# hematicComputer.net
KiCad netlist of a schematic drawn in EAGLE
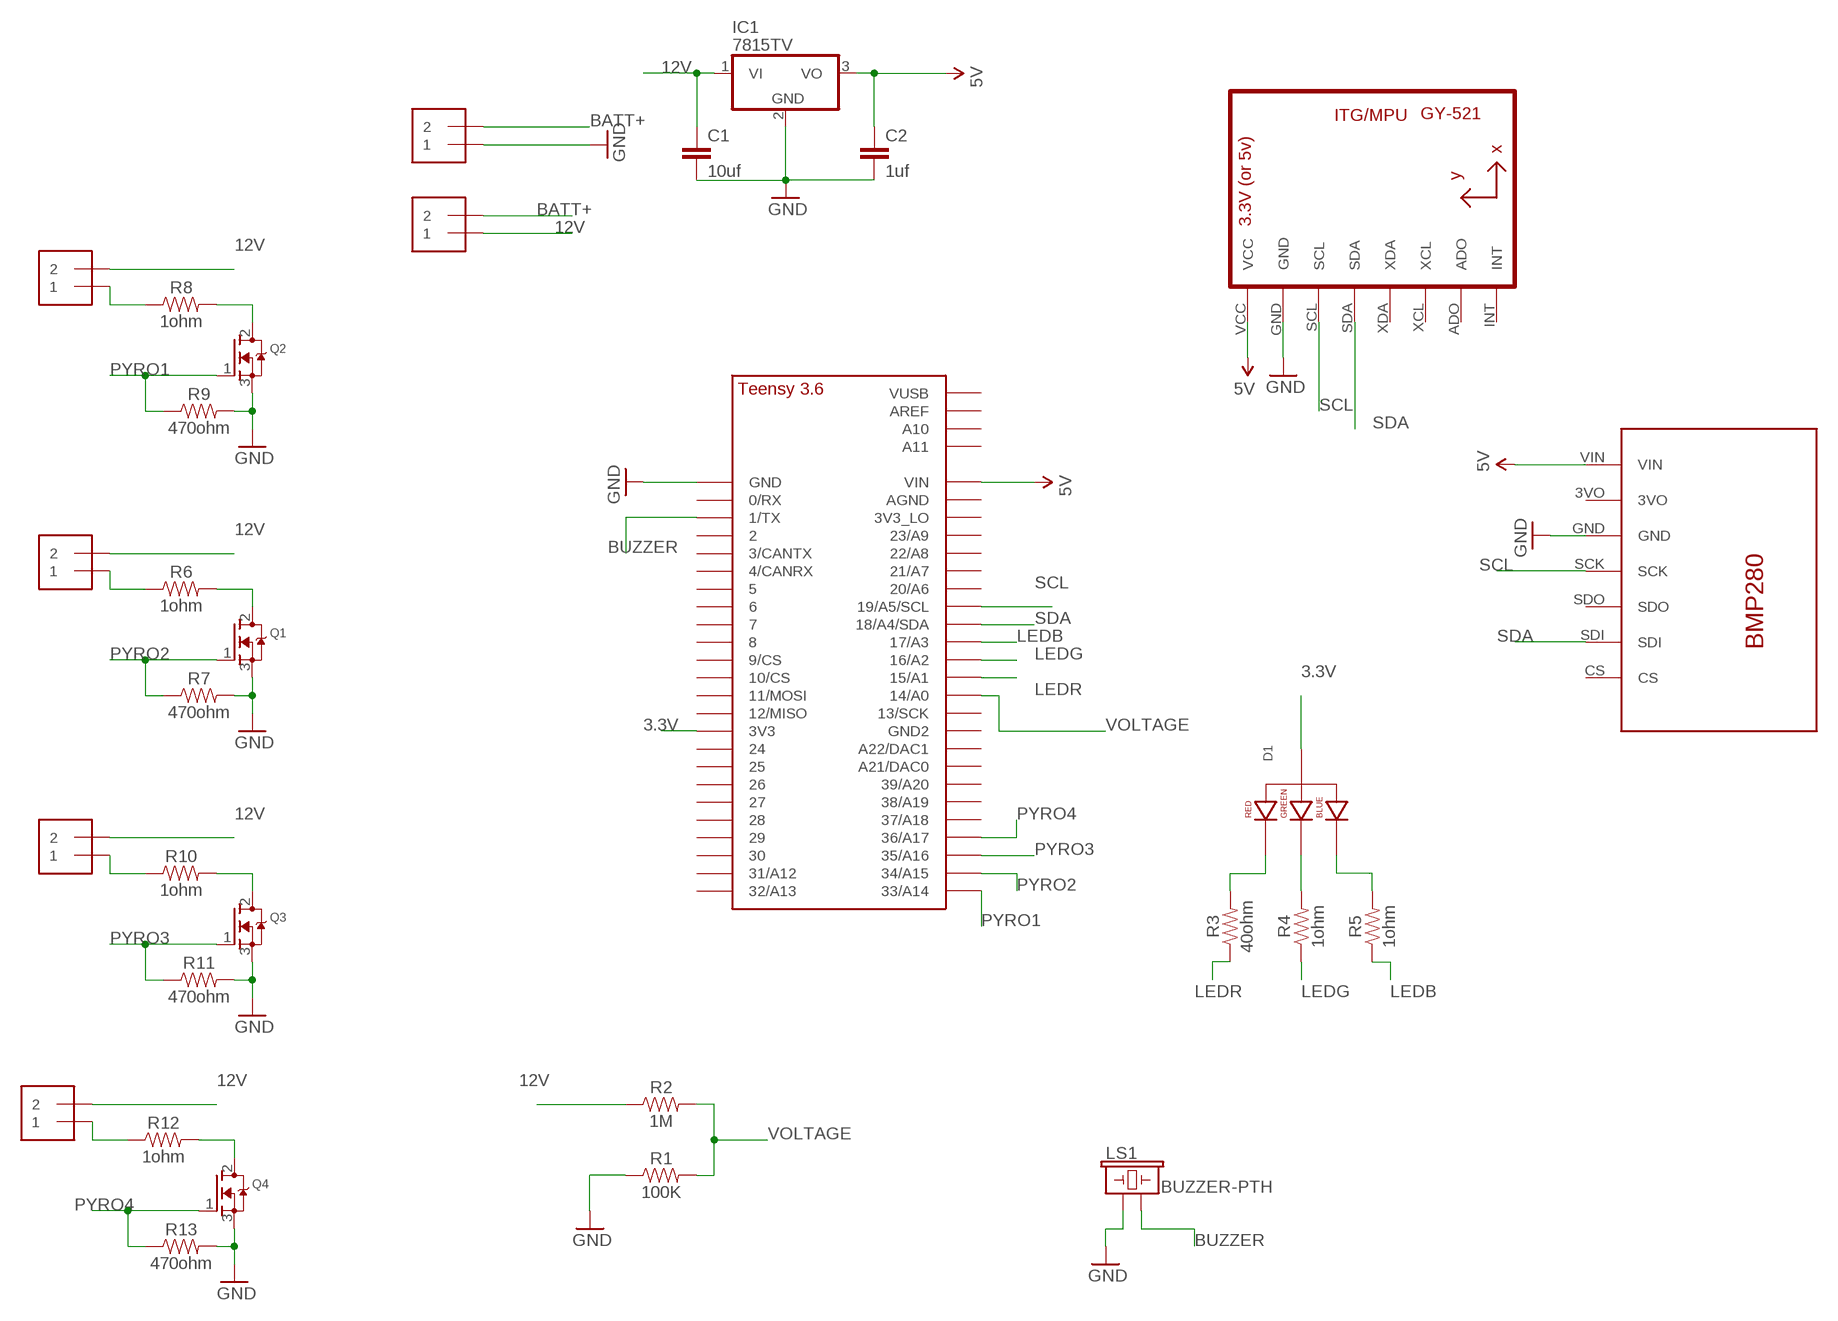
[diagram p0: schematic, sheet 1]

(export (version "E")
  (design (tool "Eeschema 10.0.6"))
  (components
    (comp (ref "C1")
      (value "10uf")
      (footprint "eagle-import:CAP-PTH-2.54")
      (libsource (lib "eagle-import") (part "22PF-PTH-2.54MM-200V-5%"))
    )
    (comp (ref "C2")
      (value "1uf")
      (footprint "eagle-import:CAP-PTH-2.54")
      (libsource (lib "eagle-import") (part "22PF-PTH-2.54MM-200V-5%"))
    )
    (comp (ref "D1")
      (value "LED-RGB-CA-THRUCLEAR")
      (footprint "eagle-import:LED-RGB-THRU")
      (libsource (lib "eagle-import") (part "LED-RGB-CA-THRUCLEAR"))
    )
    (comp (ref "IC1")
      (value "7815TV")
      (footprint "eagle-import:TO220V")
      (libsource (lib "eagle-import") (part "78TV15"))
    )
    (comp (ref "J1")
      (value "1X2-3.5MM")
      (footprint "eagle-import:1X2-3.5MM")
      (libsource (lib "eagle-import") (part "1X2-3.5MM"))
    )
    (comp (ref "J2")
      (value "1X2-3.5MM")
      (footprint "eagle-import:1X2-3.5MM")
      (libsource (lib "eagle-import") (part "1X2-3.5MM"))
    )
    (comp (ref "J3")
      (value "1X2-3.5MM")
      (footprint "eagle-import:1X2-3.5MM")
      (libsource (lib "eagle-import") (part "1X2-3.5MM"))
    )
    (comp (ref "J4")
      (value "1X2-3.5MM")
      (footprint "eagle-import:1X2-3.5MM")
      (libsource (lib "eagle-import") (part "1X2-3.5MM"))
    )
    (comp (ref "J5")
      (value "1X2-3.5MM")
      (footprint "eagle-import:1X2-3.5MM")
      (libsource (lib "eagle-import") (part "1X2-3.5MM"))
    )
    (comp (ref "J6")
      (value "1X2-3.5MM")
      (footprint "eagle-import:1X2-3.5MM")
      (libsource (lib "eagle-import") (part "1X2-3.5MM"))
    )
    (comp (ref "LS1")
      (value "BUZZER-PTH")
      (footprint "eagle-import:BUZZER-12MM")
      (libsource (lib "eagle-import") (part "BUZZER-PTH"))
    )
    (comp (ref "Q1")
      (value "MOSFET-NGDS_TO220V")
      (footprint "eagle-import:TO220V")
      (libsource (lib "eagle-import") (part "MOSFET-NGDS_TO220V"))
    )
    (comp (ref "Q2")
      (value "MOSFET-NGDS_TO220V")
      (footprint "eagle-import:TO220V")
      (libsource (lib "eagle-import") (part "MOSFET-NGDS_TO220V"))
    )
    (comp (ref "Q3")
      (value "MOSFET-NGDS_TO220V")
      (footprint "eagle-import:TO220V")
      (libsource (lib "eagle-import") (part "MOSFET-NGDS_TO220V"))
    )
    (comp (ref "Q4")
      (value "MOSFET-NGDS_TO220V")
      (footprint "eagle-import:TO220V")
      (libsource (lib "eagle-import") (part "MOSFET-NGDS_TO220V"))
    )
    (comp (ref "R1")
      (value "100K")
      (footprint "eagle-import:AXIAL-0.3")
      (libsource (lib "eagle-import") (part "10KOHM-HORIZ-1/4W-1%"))
    )
    (comp (ref "R2")
      (value "1M")
      (footprint "eagle-import:AXIAL-0.3")
      (libsource (lib "eagle-import") (part "10KOHM-HORIZ-1/4W-1%"))
    )
    (comp (ref "R3")
      (value "40ohm")
      (footprint "eagle-import:AXIAL-0.3")
      (libsource (lib "eagle-import") (part "10KOHM-HORIZ-1/4W-1%"))
    )
    (comp (ref "R4")
      (value "1ohm")
      (footprint "eagle-import:AXIAL-0.3")
      (libsource (lib "eagle-import") (part "10KOHM-HORIZ-1/4W-1%"))
    )
    (comp (ref "R5")
      (value "1ohm")
      (footprint "eagle-import:AXIAL-0.3")
      (libsource (lib "eagle-import") (part "10KOHM-HORIZ-1/4W-1%"))
    )
    (comp (ref "R6")
      (value "1ohm")
      (footprint "eagle-import:AXIAL-0.3")
      (libsource (lib "eagle-import") (part "10KOHM-HORIZ-1/4W-1%"))
    )
    (comp (ref "R7")
      (value "470ohm")
      (footprint "eagle-import:AXIAL-0.3")
      (libsource (lib "eagle-import") (part "10KOHM-HORIZ-1/4W-1%"))
    )
    (comp (ref "R8")
      (value "1ohm")
      (footprint "eagle-import:AXIAL-0.3")
      (libsource (lib "eagle-import") (part "10KOHM-HORIZ-1/4W-1%"))
    )
    (comp (ref "R9")
      (value "470ohm")
      (footprint "eagle-import:AXIAL-0.3")
      (libsource (lib "eagle-import") (part "10KOHM-HORIZ-1/4W-1%"))
    )
    (comp (ref "R10")
      (value "1ohm")
      (footprint "eagle-import:AXIAL-0.3")
      (libsource (lib "eagle-import") (part "10KOHM-HORIZ-1/4W-1%"))
    )
    (comp (ref "R11")
      (value "470ohm")
      (footprint "eagle-import:AXIAL-0.3")
      (libsource (lib "eagle-import") (part "10KOHM-HORIZ-1/4W-1%"))
    )
    (comp (ref "R12")
      (value "1ohm")
      (footprint "eagle-import:AXIAL-0.3")
      (libsource (lib "eagle-import") (part "10KOHM-HORIZ-1/4W-1%"))
    )
    (comp (ref "R13")
      (value "470ohm")
      (footprint "eagle-import:AXIAL-0.3")
      (libsource (lib "eagle-import") (part "10KOHM-HORIZ-1/4W-1%"))
    )
    (comp (ref "U$1")
      (value "TEENSY_3.5/3.6_BASIC")
      (footprint "eagle-import:TEENSY_3.5_3.6_BASIC")
      (libsource (lib "eagle-import") (part "TEENSY_3.5/3.6_BASIC"))
    )
    (comp (ref "U$2")
      (value "BMP280")
      (footprint "eagle-import:BMP280")
      (libsource (lib "eagle-import") (part "BMP280"))
    )
    (comp (ref "U1")
      (value "GY-521MPU6050")
      (footprint "eagle-import:GY-521")
      (libsource (lib "eagle-import") (part "GY-521MPU6050"))
    )
  )
  (nets
    (net (code "1") (name "/3.3V") (class "Default")
      (node (ref "D1") (pin "2") (pinfunction "ANODE_2") (pintype "bidirectional"))
      (node (ref "U$1") (pin "3V3") (pinfunction "3V3_3V3") (pintype "bidirectional"))
    )
    (net (code "2") (name "/12V") (class "Default")
      (node (ref "C1") (pin "1") (pinfunction "1_1") (pintype "passive"))
      (node (ref "IC1") (pin "1") (pinfunction "VI_1") (pintype "input"))
      (node (ref "J2") (pin "1") (pinfunction "1_1") (pintype "passive"))
      (node (ref "J3") (pin "2") (pinfunction "2_2") (pintype "passive"))
      (node (ref "J4") (pin "2") (pinfunction "2_2") (pintype "passive"))
      (node (ref "J5") (pin "2") (pinfunction "2_2") (pintype "passive"))
      (node (ref "J6") (pin "2") (pinfunction "2_2") (pintype "passive"))
      (node (ref "R2") (pin "P$1") (pinfunction "1_P$1") (pintype "passive"))
    )
    (net (code "3") (name "/BATT+") (class "Default")
      (node (ref "J1") (pin "2") (pinfunction "2_2") (pintype "passive"))
      (node (ref "J2") (pin "2") (pinfunction "2_2") (pintype "passive"))
    )
    (net (code "4") (name "/BUZZER") (class "Default")
      (node (ref "LS1") (pin "-") (pinfunction "2_-") (pintype "passive"))
      (node (ref "U$1") (pin "1/TX") (pinfunction "1/TX_1/TX") (pintype "bidirectional"))
    )
    (net (code "5") (name "/LEDB") (class "Default")
      (node (ref "R5") (pin "P$1") (pinfunction "1_P$1") (pintype "passive"))
      (node (ref "U$1") (pin "17/A3") (pinfunction "17/A3_17/A3") (pintype "bidirectional"))
    )
    (net (code "6") (name "/LEDG") (class "Default")
      (node (ref "R4") (pin "P$1") (pinfunction "1_P$1") (pintype "passive"))
      (node (ref "U$1") (pin "16/A2") (pinfunction "16/A2_16/A2") (pintype "bidirectional"))
    )
    (net (code "7") (name "/LEDR") (class "Default")
      (node (ref "R3") (pin "P$1") (pinfunction "1_P$1") (pintype "passive"))
      (node (ref "U$1") (pin "15/A1") (pinfunction "15/A1_15/A1") (pintype "bidirectional"))
    )
    (net (code "8") (name "/PYRO1") (class "Default")
      (node (ref "Q2") (pin "1") (pinfunction "G_1") (pintype "bidirectional"))
      (node (ref "R9") (pin "P$1") (pinfunction "1_P$1") (pintype "passive"))
      (node (ref "U$1") (pin "33/A14") (pinfunction "33/A14_33/A14") (pintype "bidirectional"))
    )
    (net (code "9") (name "/PYRO2") (class "Default")
      (node (ref "Q1") (pin "1") (pinfunction "G_1") (pintype "bidirectional"))
      (node (ref "R7") (pin "P$1") (pinfunction "1_P$1") (pintype "passive"))
      (node (ref "U$1") (pin "34/A15") (pinfunction "34/A15_34/A15") (pintype "bidirectional"))
    )
    (net (code "10") (name "/PYRO3") (class "Default")
      (node (ref "Q3") (pin "1") (pinfunction "G_1") (pintype "bidirectional"))
      (node (ref "R11") (pin "P$1") (pinfunction "1_P$1") (pintype "passive"))
      (node (ref "U$1") (pin "35/A16") (pinfunction "35/A16_35/A16") (pintype "bidirectional"))
    )
    (net (code "11") (name "/PYRO4") (class "Default")
      (node (ref "Q4") (pin "1") (pinfunction "G_1") (pintype "bidirectional"))
      (node (ref "R13") (pin "P$1") (pinfunction "1_P$1") (pintype "passive"))
      (node (ref "U$1") (pin "36/A17") (pinfunction "36/A17_36/A17") (pintype "bidirectional"))
    )
    (net (code "12") (name "/SCL") (class "Default")
      (node (ref "U$1") (pin "19/A5/SCL") (pinfunction "19/A5/SCL_19/A5/SCL") (pintype "bidirectional"))
      (node (ref "U$2") (pin "SCK") (pinfunction "SCK_SCK") (pintype "bidirectional"))
      (node (ref "U1") (pin "SCL") (pinfunction "SCL_SCL") (pintype "bidirectional"))
    )
    (net (code "13") (name "/SDA") (class "Default")
      (node (ref "U$1") (pin "18/A4/SDA") (pinfunction "18/A4/SDA_18/A4/SDA") (pintype "bidirectional"))
      (node (ref "U$2") (pin "SDI") (pinfunction "SDI_SDI") (pintype "bidirectional"))
      (node (ref "U1") (pin "SDA") (pinfunction "SDA_SDA") (pintype "bidirectional"))
    )
    (net (code "14") (name "/VOLTAGE") (class "Default")
      (node (ref "R1") (pin "P$2") (pinfunction "2_P$2") (pintype "passive"))
      (node (ref "R2") (pin "P$2") (pinfunction "2_P$2") (pintype "passive"))
      (node (ref "U$1") (pin "14/A0") (pinfunction "14/A0_14/A0") (pintype "bidirectional"))
    )
    (net (code "15") (name "5V") (class "Default")
      (node (ref "C2") (pin "1") (pinfunction "1_1") (pintype "passive"))
      (node (ref "IC1") (pin "3") (pinfunction "VO_3") (pintype "passive"))
      (node (ref "U$1") (pin "VIN") (pinfunction "VIN_VIN") (pintype "bidirectional"))
      (node (ref "U$2") (pin "VIN") (pinfunction "VIN_VIN") (pintype "bidirectional"))
      (node (ref "U1") (pin "VCC") (pinfunction "VCC_VCC") (pintype "bidirectional"))
    )
    (net (code "16") (name "GND") (class "Default")
      (node (ref "C1") (pin "2") (pinfunction "2_2") (pintype "passive"))
      (node (ref "C2") (pin "2") (pinfunction "2_2") (pintype "passive"))
      (node (ref "IC1") (pin "2") (pinfunction "GND_2") (pintype "passive"))
      (node (ref "J1") (pin "1") (pinfunction "1_1") (pintype "passive"))
      (node (ref "LS1") (pin "+") (pinfunction "1_+") (pintype "passive"))
      (node (ref "Q1") (pin "3") (pinfunction "S_3") (pintype "bidirectional"))
      (node (ref "Q2") (pin "3") (pinfunction "S_3") (pintype "bidirectional"))
      (node (ref "Q3") (pin "3") (pinfunction "S_3") (pintype "bidirectional"))
      (node (ref "Q4") (pin "3") (pinfunction "S_3") (pintype "bidirectional"))
      (node (ref "R1") (pin "P$1") (pinfunction "1_P$1") (pintype "passive"))
      (node (ref "R11") (pin "P$2") (pinfunction "2_P$2") (pintype "passive"))
      (node (ref "R13") (pin "P$2") (pinfunction "2_P$2") (pintype "passive"))
      (node (ref "R7") (pin "P$2") (pinfunction "2_P$2") (pintype "passive"))
      (node (ref "R9") (pin "P$2") (pinfunction "2_P$2") (pintype "passive"))
      (node (ref "U$1") (pin "GND") (pinfunction "GND_GND") (pintype "bidirectional"))
      (node (ref "U$2") (pin "GND") (pinfunction "GND_GND") (pintype "bidirectional"))
      (node (ref "U1") (pin "GND") (pinfunction "GND_GND") (pintype "bidirectional"))
    )
    (net (code "17") (name "Net-(D1-BLUE_CATHODE)") (class "Default")
      (node (ref "D1") (pin "4") (pinfunction "BLUE_CATHODE_4") (pintype "bidirectional"))
      (node (ref "R5") (pin "P$2") (pinfunction "2_P$2") (pintype "passive"))
    )
    (net (code "18") (name "Net-(D1-GREEN_CATHODE)") (class "Default")
      (node (ref "D1") (pin "3") (pinfunction "GREEN_CATHODE_3") (pintype "bidirectional"))
      (node (ref "R4") (pin "P$2") (pinfunction "2_P$2") (pintype "passive"))
    )
    (net (code "19") (name "Net-(D1-RED_CATHODE)") (class "Default")
      (node (ref "D1") (pin "1") (pinfunction "RED_CATHODE_1") (pintype "bidirectional"))
      (node (ref "R3") (pin "P$2") (pinfunction "2_P$2") (pintype "passive"))
    )
    (net (code "20") (name "Net-(Q1-D)") (class "Default")
      (node (ref "Q1") (pin "2") (pinfunction "D_2") (pintype "bidirectional"))
      (node (ref "R6") (pin "P$2") (pinfunction "2_P$2") (pintype "passive"))
    )
    (net (code "21") (name "Net-(Q2-D)") (class "Default")
      (node (ref "Q2") (pin "2") (pinfunction "D_2") (pintype "bidirectional"))
      (node (ref "R8") (pin "P$2") (pinfunction "2_P$2") (pintype "passive"))
    )
    (net (code "22") (name "Net-(Q3-D)") (class "Default")
      (node (ref "Q3") (pin "2") (pinfunction "D_2") (pintype "bidirectional"))
      (node (ref "R10") (pin "P$2") (pinfunction "2_P$2") (pintype "passive"))
    )
    (net (code "23") (name "Net-(Q4-D)") (class "Default")
      (node (ref "Q4") (pin "2") (pinfunction "D_2") (pintype "bidirectional"))
      (node (ref "R12") (pin "P$2") (pinfunction "2_P$2") (pintype "passive"))
    )
    (net (code "24") (name "Net-(R6-1)") (class "Default")
      (node (ref "J6") (pin "1") (pinfunction "1_1") (pintype "passive"))
      (node (ref "R6") (pin "P$1") (pinfunction "1_P$1") (pintype "passive"))
    )
    (net (code "25") (name "Net-(R8-1)") (class "Default")
      (node (ref "J3") (pin "1") (pinfunction "1_1") (pintype "passive"))
      (node (ref "R8") (pin "P$1") (pinfunction "1_P$1") (pintype "passive"))
    )
    (net (code "26") (name "Net-(R10-1)") (class "Default")
      (node (ref "J4") (pin "1") (pinfunction "1_1") (pintype "passive"))
      (node (ref "R10") (pin "P$1") (pinfunction "1_P$1") (pintype "passive"))
    )
    (net (code "27") (name "Net-(R12-1)") (class "Default")
      (node (ref "J5") (pin "1") (pinfunction "1_1") (pintype "passive"))
      (node (ref "R12") (pin "P$1") (pinfunction "1_P$1") (pintype "passive"))
    )
    (net (code "28") (name "unconnected-(U$1-A21{slash}DAC0-Pad21{slash}DAC0)") (class "Default")
      (node (ref "U$1") (pin "21/DAC0") (pinfunction "A21/DAC0_21/DAC0") (pintype "bidirectional"))
    )
    (net (code "29") (name "unconnected-(U$1-Pad0{slash}RX)") (class "Default")
      (node (ref "U$1") (pin "0/RX") (pinfunction "0/RX_0/RX") (pintype "bidirectional"))
    )
    (net (code "30") (name "unconnected-(U$1-Pad2)") (class "Default")
      (node (ref "U$1") (pin "2") (pinfunction "2_2") (pintype "bidirectional"))
    )
    (net (code "31") (name "unconnected-(U$1-Pad3V3_LO)") (class "Default")
      (node (ref "U$1") (pin "3V3_LO") (pinfunction "3V3_LO_3V3_LO") (pintype "bidirectional"))
    )
    (net (code "32") (name "unconnected-(U$1-Pad3{slash}CANTX)") (class "Default")
      (node (ref "U$1") (pin "3/CANTX") (pinfunction "3/CANTX_3/CANTX") (pintype "bidirectional"))
    )
    (net (code "33") (name "unconnected-(U$1-Pad4{slash}CANRX)") (class "Default")
      (node (ref "U$1") (pin "4/CANRX") (pinfunction "4/CANRX_4/CANRX") (pintype "bidirectional"))
    )
    (net (code "34") (name "unconnected-(U$1-Pad5)") (class "Default")
      (node (ref "U$1") (pin "5") (pinfunction "5_5") (pintype "bidirectional"))
    )
    (net (code "35") (name "unconnected-(U$1-Pad6)") (class "Default")
      (node (ref "U$1") (pin "6") (pinfunction "6_6") (pintype "bidirectional"))
    )
    (net (code "36") (name "unconnected-(U$1-Pad7)") (class "Default")
      (node (ref "U$1") (pin "7") (pinfunction "7_7") (pintype "bidirectional"))
    )
    (net (code "37") (name "unconnected-(U$1-Pad8)") (class "Default")
      (node (ref "U$1") (pin "8") (pinfunction "8_8") (pintype "bidirectional"))
    )
    (net (code "38") (name "unconnected-(U$1-Pad9{slash}CS)") (class "Default")
      (node (ref "U$1") (pin "9/CS") (pinfunction "9/CS_9/CS") (pintype "bidirectional"))
    )
    (net (code "39") (name "unconnected-(U$1-Pad10{slash}CS)") (class "Default")
      (node (ref "U$1") (pin "10/CS") (pinfunction "10/CS_10/CS") (pintype "bidirectional"))
    )
    (net (code "40") (name "unconnected-(U$1-Pad11{slash}MOSI)") (class "Default")
      (node (ref "U$1") (pin "11/MOSI") (pinfunction "11/MOSI_11/MOSI") (pintype "bidirectional"))
    )
    (net (code "41") (name "unconnected-(U$1-Pad12{slash}MISO)") (class "Default")
      (node (ref "U$1") (pin "12/MISO") (pinfunction "12/MISO_12/MISO") (pintype "bidirectional"))
    )
    (net (code "42") (name "unconnected-(U$1-Pad13{slash}SCK)") (class "Default")
      (node (ref "U$1") (pin "13/SCK") (pinfunction "13/SCK_13/SCK") (pintype "bidirectional"))
    )
    (net (code "43") (name "unconnected-(U$1-Pad20{slash}A6)") (class "Default")
      (node (ref "U$1") (pin "20/A6") (pinfunction "20/A6_20/A6") (pintype "bidirectional"))
    )
    (net (code "44") (name "unconnected-(U$1-Pad21{slash}A7)") (class "Default")
      (node (ref "U$1") (pin "21/A7") (pinfunction "21/A7_21/A7") (pintype "bidirectional"))
    )
    (net (code "45") (name "unconnected-(U$1-Pad22{slash}A8)") (class "Default")
      (node (ref "U$1") (pin "22/A8") (pinfunction "22/A8_22/A8") (pintype "bidirectional"))
    )
    (net (code "46") (name "unconnected-(U$1-Pad23{slash}A9)") (class "Default")
      (node (ref "U$1") (pin "23/A9") (pinfunction "23/A9_23/A9") (pintype "bidirectional"))
    )
    (net (code "47") (name "unconnected-(U$1-Pad24)") (class "Default")
      (node (ref "U$1") (pin "24") (pinfunction "24_24") (pintype "bidirectional"))
    )
    (net (code "48") (name "unconnected-(U$1-Pad25)") (class "Default")
      (node (ref "U$1") (pin "25") (pinfunction "25_25") (pintype "bidirectional"))
    )
    (net (code "49") (name "unconnected-(U$1-Pad26)") (class "Default")
      (node (ref "U$1") (pin "26") (pinfunction "26_26") (pintype "bidirectional"))
    )
    (net (code "50") (name "unconnected-(U$1-Pad27)") (class "Default")
      (node (ref "U$1") (pin "27") (pinfunction "27_27") (pintype "bidirectional"))
    )
    (net (code "51") (name "unconnected-(U$1-Pad28)") (class "Default")
      (node (ref "U$1") (pin "28") (pinfunction "28_28") (pintype "bidirectional"))
    )
    (net (code "52") (name "unconnected-(U$1-Pad29)") (class "Default")
      (node (ref "U$1") (pin "29") (pinfunction "29_29") (pintype "bidirectional"))
    )
    (net (code "53") (name "unconnected-(U$1-Pad30)") (class "Default")
      (node (ref "U$1") (pin "30") (pinfunction "30_30") (pintype "bidirectional"))
    )
    (net (code "54") (name "unconnected-(U$1-Pad31{slash}A12)") (class "Default")
      (node (ref "U$1") (pin "31/A12") (pinfunction "31/A12_31/A12") (pintype "bidirectional"))
    )
    (net (code "55") (name "unconnected-(U$1-Pad32{slash}A13)") (class "Default")
      (node (ref "U$1") (pin "32/A13") (pinfunction "32/A13_32/A13") (pintype "bidirectional"))
    )
    (net (code "56") (name "unconnected-(U$1-Pad37{slash}A18)") (class "Default")
      (node (ref "U$1") (pin "37/A18") (pinfunction "37/A18_37/A18") (pintype "bidirectional"))
    )
    (net (code "57") (name "unconnected-(U$1-Pad38{slash}A19)") (class "Default")
      (node (ref "U$1") (pin "38/A19") (pinfunction "38/A19_38/A19") (pintype "bidirectional"))
    )
    (net (code "58") (name "unconnected-(U$1-Pad39{slash}A20)") (class "Default")
      (node (ref "U$1") (pin "39/A20") (pinfunction "39/A20_39/A20") (pintype "bidirectional"))
    )
    (net (code "59") (name "unconnected-(U$1-PadA10)") (class "Default")
      (node (ref "U$1") (pin "A10") (pinfunction "A10_A10") (pintype "bidirectional"))
    )
    (net (code "60") (name "unconnected-(U$1-PadA11)") (class "Default")
      (node (ref "U$1") (pin "A11") (pinfunction "A11_A11") (pintype "bidirectional"))
    )
    (net (code "61") (name "unconnected-(U$1-PadA22{slash}DAC1)") (class "Default")
      (node (ref "U$1") (pin "A22/DAC1") (pinfunction "A22/DAC1_A22/DAC1") (pintype "bidirectional"))
    )
    (net (code "62") (name "unconnected-(U$1-PadAGND)") (class "Default")
      (node (ref "U$1") (pin "AGND") (pinfunction "AGND_AGND") (pintype "bidirectional"))
    )
    (net (code "63") (name "unconnected-(U$1-PadAREF)") (class "Default")
      (node (ref "U$1") (pin "AREF") (pinfunction "AREF_AREF") (pintype "bidirectional"))
    )
    (net (code "64") (name "unconnected-(U$1-PadGND2)") (class "Default")
      (node (ref "U$1") (pin "GND2") (pinfunction "GND2_GND2") (pintype "bidirectional"))
    )
    (net (code "65") (name "unconnected-(U$1-PadVUSB)") (class "Default")
      (node (ref "U$1") (pin "VUSB") (pinfunction "VUSB_VUSB") (pintype "bidirectional"))
    )
    (net (code "66") (name "unconnected-(U$2-Pad3VO)") (class "Default")
      (node (ref "U$2") (pin "3VO") (pinfunction "3VO_3VO") (pintype "bidirectional"))
    )
    (net (code "67") (name "unconnected-(U$2-PadCS)") (class "Default")
      (node (ref "U$2") (pin "CS") (pinfunction "CS_CS") (pintype "bidirectional"))
    )
    (net (code "68") (name "unconnected-(U$2-PadSDO)") (class "Default")
      (node (ref "U$2") (pin "SDO") (pinfunction "SDO_SDO") (pintype "bidirectional"))
    )
    (net (code "69") (name "unconnected-(U1-PadADO)") (class "Default")
      (node (ref "U1") (pin "ADO") (pinfunction "ADO_ADO") (pintype "bidirectional"))
    )
    (net (code "70") (name "unconnected-(U1-PadINT)") (class "Default")
      (node (ref "U1") (pin "INT") (pinfunction "INT_INT") (pintype "bidirectional"))
    )
    (net (code "71") (name "unconnected-(U1-PadXCL)") (class "Default")
      (node (ref "U1") (pin "XCL") (pinfunction "XCL_XCL") (pintype "bidirectional"))
    )
    (net (code "72") (name "unconnected-(U1-PadXDA)") (class "Default")
      (node (ref "U1") (pin "XDA") (pinfunction "XDA_XDA") (pintype "bidirectional"))
    )
  )
)
